# B360C.net
KiCad netlist of a schematic drawn in EAGLE
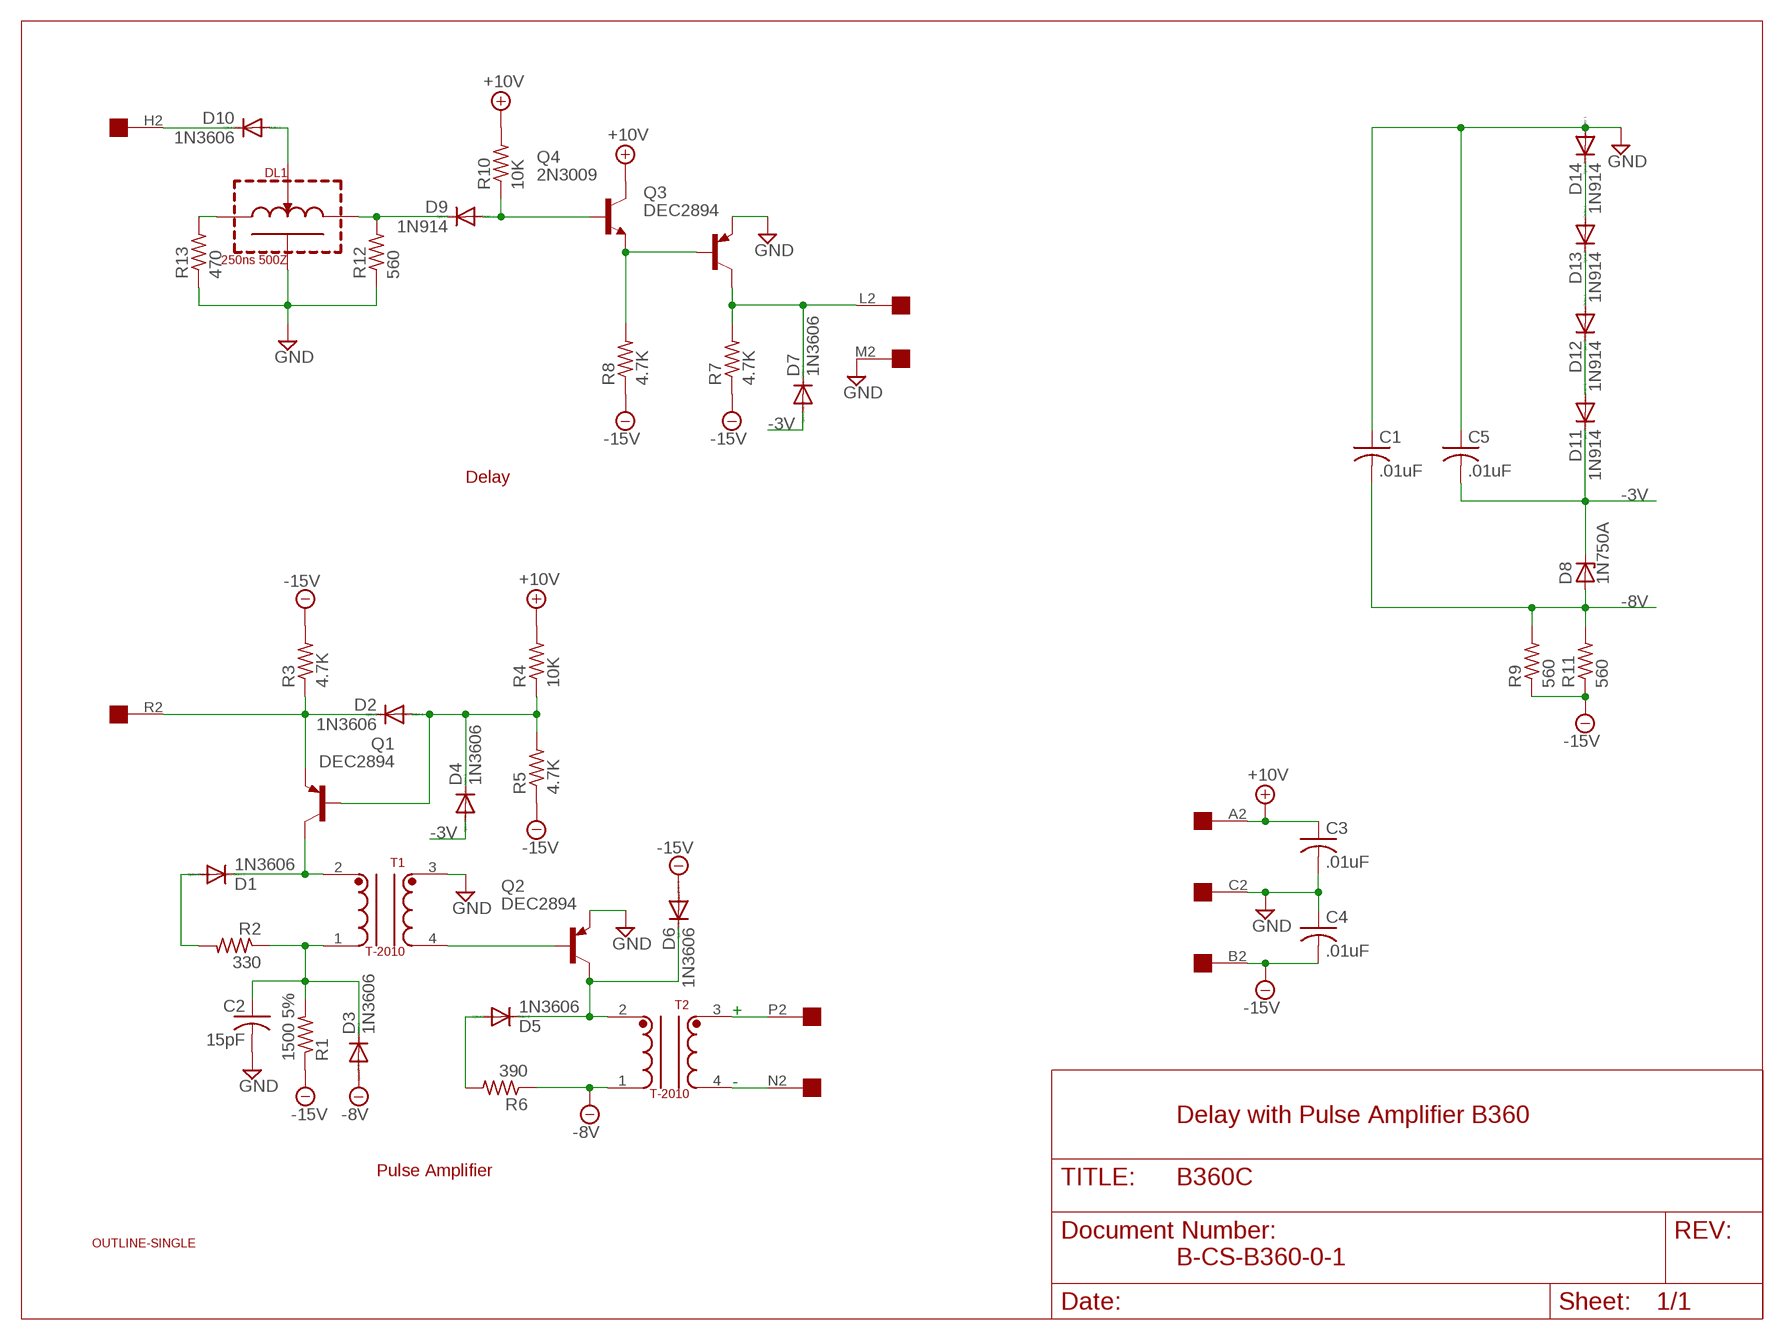
[diagram p0: schematic, sheet 1]

(export (version "E")
  (design (tool "Eeschema 10.0.6"))
  (components
    (comp (ref "C1")
      (value ".01uF")
      (footprint "eagle-import:C050-025X075")
      (libsource (lib "eagle-import") (part "C-US050-025X075"))
    )
    (comp (ref "C2")
      (value "15pF")
      (footprint "eagle-import:C050-025X075")
      (libsource (lib "eagle-import") (part "C-US050-025X075"))
    )
    (comp (ref "C3")
      (value ".01uF")
      (footprint "eagle-import:C050-025X075")
      (libsource (lib "eagle-import") (part "C-US050-025X075"))
    )
    (comp (ref "C4")
      (value ".01uF")
      (footprint "eagle-import:C050-025X075")
      (libsource (lib "eagle-import") (part "C-US050-025X075"))
    )
    (comp (ref "C5")
      (value ".01uF")
      (footprint "eagle-import:C050-025X075")
      (libsource (lib "eagle-import") (part "C-US050-025X075"))
    )
    (comp (ref "D1")
      (value "1N3606")
      (footprint "eagle-import:DO35-10")
      (libsource (lib "eagle-import") (part "1N4148DO35-10"))
    )
    (comp (ref "D2")
      (value "1N3606")
      (footprint "eagle-import:DO35-10")
      (libsource (lib "eagle-import") (part "1N4148DO35-10"))
    )
    (comp (ref "D3")
      (value "1N3606")
      (footprint "eagle-import:DO35-10")
      (libsource (lib "eagle-import") (part "1N4148DO35-10"))
    )
    (comp (ref "D4")
      (value "1N3606")
      (footprint "eagle-import:DO35-10")
      (libsource (lib "eagle-import") (part "1N4148DO35-10"))
    )
    (comp (ref "D5")
      (value "1N3606")
      (footprint "eagle-import:DO35-10")
      (libsource (lib "eagle-import") (part "1N4148DO35-10"))
    )
    (comp (ref "D6")
      (value "1N3606")
      (footprint "eagle-import:DO35-10")
      (libsource (lib "eagle-import") (part "1N4148DO35-10"))
    )
    (comp (ref "D7")
      (value "1N3606")
      (footprint "eagle-import:DO35-10")
      (libsource (lib "eagle-import") (part "1N4148DO35-10"))
    )
    (comp (ref "D8")
      (value "1N750A")
      (footprint "eagle-import:DO35Z10")
      (libsource (lib "eagle-import") (part "ZENER-DIODEDO35Z10"))
    )
    (comp (ref "D9")
      (value "1N914")
      (footprint "eagle-import:DO35-10")
      (libsource (lib "eagle-import") (part "1N4148DO35-10"))
    )
    (comp (ref "D10")
      (value "1N3606")
      (footprint "eagle-import:DO35-10")
      (libsource (lib "eagle-import") (part "1N4148DO35-10"))
    )
    (comp (ref "D11")
      (value "1N914")
      (footprint "eagle-import:DO35-10")
      (libsource (lib "eagle-import") (part "1N4148DO35-10"))
    )
    (comp (ref "D12")
      (value "1N914")
      (footprint "eagle-import:DO35-10")
      (libsource (lib "eagle-import") (part "1N4148DO35-10"))
    )
    (comp (ref "D13")
      (value "1N914")
      (footprint "eagle-import:DO35-10")
      (libsource (lib "eagle-import") (part "1N4148DO35-10"))
    )
    (comp (ref "D14")
      (value "1N914")
      (footprint "eagle-import:DO35-10")
      (libsource (lib "eagle-import") (part "1N4148DO35-10"))
    )
    (comp (ref "DL1")
      (value "250ns 500Z")
      (footprint "eagle-import:DELAYLINE")
      (libsource (lib "eagle-import") (part "DELAYLINE"))
    )
    (comp (ref "Q1")
      (value "DEC2894")
      (footprint "eagle-import:TO39")
      (libsource (lib "eagle-import") (part "2N2904"))
    )
    (comp (ref "Q2")
      (value "DEC2894")
      (footprint "eagle-import:TO39")
      (libsource (lib "eagle-import") (part "2N2904"))
    )
    (comp (ref "Q3")
      (value "DEC2894")
      (footprint "eagle-import:TO39")
      (libsource (lib "eagle-import") (part "2N2904"))
    )
    (comp (ref "Q4")
      (value "2N3009")
      (footprint "eagle-import:TO39")
      (libsource (lib "eagle-import") (part "-NPN-TO39-EBC2N2102"))
    )
    (comp (ref "R1")
      (value "1500 5%")
      (footprint "eagle-import:0207_10")
      (libsource (lib "eagle-import") (part "R-US_0207/10"))
    )
    (comp (ref "R2")
      (value "330")
      (footprint "eagle-import:0207_10")
      (libsource (lib "eagle-import") (part "R-US_0207/10"))
    )
    (comp (ref "R3")
      (value "4.7K")
      (footprint "eagle-import:0207_10")
      (libsource (lib "eagle-import") (part "R-US_0207/10"))
    )
    (comp (ref "R4")
      (value "10K")
      (footprint "eagle-import:0207_10")
      (libsource (lib "eagle-import") (part "R-US_0207/10"))
    )
    (comp (ref "R5")
      (value "4.7K")
      (footprint "eagle-import:0207_10")
      (libsource (lib "eagle-import") (part "R-US_0207/10"))
    )
    (comp (ref "R6")
      (value "390")
      (footprint "eagle-import:0207_10")
      (libsource (lib "eagle-import") (part "R-US_0207/10"))
    )
    (comp (ref "R7")
      (value "4.7K")
      (footprint "eagle-import:0207_10")
      (libsource (lib "eagle-import") (part "R-US_0207/10"))
    )
    (comp (ref "R8")
      (value "4.7K")
      (footprint "eagle-import:0207_10")
      (libsource (lib "eagle-import") (part "R-US_0207/10"))
    )
    (comp (ref "R9")
      (value "560")
      (footprint "eagle-import:0207_10")
      (libsource (lib "eagle-import") (part "R-US_0207/10"))
    )
    (comp (ref "R10")
      (value "10K")
      (footprint "eagle-import:0207_10")
      (libsource (lib "eagle-import") (part "R-US_0207/10"))
    )
    (comp (ref "R11")
      (value "560")
      (footprint "eagle-import:0207_10")
      (libsource (lib "eagle-import") (part "R-US_0207/10"))
    )
    (comp (ref "R12")
      (value "560")
      (footprint "eagle-import:0207_10")
      (libsource (lib "eagle-import") (part "R-US_0207/10"))
    )
    (comp (ref "R13")
      (value "470")
      (footprint "eagle-import:0207_10")
      (libsource (lib "eagle-import") (part "R-US_0207/10"))
    )
    (comp (ref "T1")
      (value "T-2010")
      (footprint "eagle-import:TRANSFORMER2")
      (libsource (lib "eagle-import") (part "T-2010"))
    )
    (comp (ref "T2")
      (value "T-2010")
      (footprint "eagle-import:TRANSFORMER2")
      (libsource (lib "eagle-import") (part "T-2010"))
    )
    (comp (ref "U$1")
      (value "OUTLINE-SINGLE")
      (footprint "eagle-import:SINGLE")
      (libsource (lib "eagle-import") (part "OUTLINE-SINGLE"))
    )
    (comp (ref "U$2")
      (value "EDGE-1")
      (footprint "eagle-import:EDGE-CON1")
      (libsource (lib "eagle-import") (part "EDGE-1"))
    )
  )
  (nets
    (net (code "1") (name "+10V") (class "Default")
      (node (ref "C3") (pin "1") (pinfunction "1_1") (pintype "passive"))
      (node (ref "Q4") (pin "3") (pinfunction "C_3") (pintype "passive"))
      (node (ref "R10") (pin "2") (pinfunction "2_2") (pintype "passive"))
      (node (ref "R4") (pin "2") (pinfunction "2_2") (pintype "passive"))
      (node (ref "U$2") (pin "A2") (pinfunction "1_A2") (pintype "bidirectional"))
    )
    (net (code "2") (name "-8V") (class "Default")
      (node (ref "C1") (pin "2") (pinfunction "2_2") (pintype "passive"))
      (node (ref "D3") (pin "A") (pinfunction "A_A") (pintype "passive"))
      (node (ref "D8") (pin "A") (pinfunction "A_A") (pintype "passive"))
      (node (ref "R11") (pin "2") (pinfunction "2_2") (pintype "passive"))
      (node (ref "R6") (pin "1") (pinfunction "1_1") (pintype "passive"))
      (node (ref "R9") (pin "2") (pinfunction "2_2") (pintype "passive"))
      (node (ref "T2") (pin "1") (pinfunction "P$5_1") (pintype "passive"))
    )
    (net (code "3") (name "-15V") (class "Default")
      (node (ref "C4") (pin "2") (pinfunction "2_2") (pintype "passive"))
      (node (ref "D6") (pin "A") (pinfunction "A_A") (pintype "passive"))
      (node (ref "R1") (pin "1") (pinfunction "1_1") (pintype "passive"))
      (node (ref "R11") (pin "1") (pinfunction "1_1") (pintype "passive"))
      (node (ref "R3") (pin "2") (pinfunction "2_2") (pintype "passive"))
      (node (ref "R5") (pin "1") (pinfunction "1_1") (pintype "passive"))
      (node (ref "R7") (pin "1") (pinfunction "1_1") (pintype "passive"))
      (node (ref "R8") (pin "1") (pinfunction "1_1") (pintype "passive"))
      (node (ref "R9") (pin "1") (pinfunction "1_1") (pintype "passive"))
      (node (ref "U$2") (pin "B2") (pinfunction "1_B2") (pintype "bidirectional"))
    )
    (net (code "4") (name "/-3V") (class "Default")
      (node (ref "C5") (pin "2") (pinfunction "2_2") (pintype "passive"))
      (node (ref "D11") (pin "C") (pinfunction "C_C") (pintype "passive"))
      (node (ref "D4") (pin "A") (pinfunction "A_A") (pintype "passive"))
      (node (ref "D7") (pin "A") (pinfunction "A_A") (pintype "passive"))
      (node (ref "D8") (pin "C") (pinfunction "C_C") (pintype "passive"))
    )
    (net (code "5") (name "GND") (class "Default")
      (node (ref "C1") (pin "1") (pinfunction "1_1") (pintype "passive"))
      (node (ref "C2") (pin "2") (pinfunction "2_2") (pintype "passive"))
      (node (ref "C3") (pin "2") (pinfunction "2_2") (pintype "passive"))
      (node (ref "C4") (pin "1") (pinfunction "1_1") (pintype "passive"))
      (node (ref "C5") (pin "1") (pinfunction "1_1") (pintype "passive"))
      (node (ref "D14") (pin "A") (pinfunction "A_A") (pintype "passive"))
      (node (ref "DL1") (pin "G") (pinfunction "G_G") (pintype "passive"))
      (node (ref "Q2") (pin "1") (pinfunction "E_1") (pintype "passive"))
      (node (ref "Q3") (pin "1") (pinfunction "E_1") (pintype "passive"))
      (node (ref "R12") (pin "1") (pinfunction "1_1") (pintype "passive"))
      (node (ref "R13") (pin "1") (pinfunction "1_1") (pintype "passive"))
      (node (ref "T1") (pin "3") (pinfunction "P$2_3") (pintype "passive"))
      (node (ref "U$2") (pin "C2") (pinfunction "1_C2") (pintype "bidirectional"))
      (node (ref "U$2") (pin "M2") (pinfunction "1_M2") (pintype "bidirectional"))
    )
    (net (code "6") (name "Net-(D1-PadA)") (class "Default")
      (node (ref "D1") (pin "A") (pinfunction "A_A") (pintype "passive"))
      (node (ref "R2") (pin "2") (pinfunction "2_2") (pintype "passive"))
    )
    (net (code "7") (name "Net-(D5-PadA)") (class "Default")
      (node (ref "D5") (pin "A") (pinfunction "A_A") (pintype "passive"))
      (node (ref "R6") (pin "2") (pinfunction "2_2") (pintype "passive"))
    )
    (net (code "8") (name "Net-(D9-PadC)") (class "Default")
      (node (ref "D9") (pin "C") (pinfunction "C_C") (pintype "passive"))
      (node (ref "DL1") (pin "L") (pinfunction "L_L") (pintype "passive"))
      (node (ref "R12") (pin "2") (pinfunction "2_2") (pintype "passive"))
    )
    (net (code "9") (name "Net-(D10-PadA)") (class "Default")
      (node (ref "D10") (pin "A") (pinfunction "A_A") (pintype "passive"))
      (node (ref "DL1") (pin "V") (pinfunction "V_V") (pintype "passive"))
    )
    (net (code "10") (name "Net-(D11-PadA)") (class "Default")
      (node (ref "D11") (pin "A") (pinfunction "A_A") (pintype "passive"))
      (node (ref "D12") (pin "C") (pinfunction "C_C") (pintype "passive"))
    )
    (net (code "11") (name "Net-(D12-PadA)") (class "Default")
      (node (ref "D12") (pin "A") (pinfunction "A_A") (pintype "passive"))
      (node (ref "D13") (pin "C") (pinfunction "C_C") (pintype "passive"))
    )
    (net (code "12") (name "Net-(D13-PadA)") (class "Default")
      (node (ref "D13") (pin "A") (pinfunction "A_A") (pintype "passive"))
      (node (ref "D14") (pin "C") (pinfunction "C_C") (pintype "passive"))
    )
    (net (code "13") (name "Net-(DL1-PadR)") (class "Default")
      (node (ref "DL1") (pin "R") (pinfunction "R_R") (pintype "passive"))
      (node (ref "R13") (pin "2") (pinfunction "2_2") (pintype "passive"))
    )
    (net (code "14") (name "Net-(Q1-B)") (class "Default")
      (node (ref "D2") (pin "A") (pinfunction "A_A") (pintype "passive"))
      (node (ref "D4") (pin "C") (pinfunction "C_C") (pintype "passive"))
      (node (ref "Q1") (pin "2") (pinfunction "B_2") (pintype "passive"))
      (node (ref "R4") (pin "1") (pinfunction "1_1") (pintype "passive"))
      (node (ref "R5") (pin "2") (pinfunction "2_2") (pintype "passive"))
    )
    (net (code "15") (name "Net-(Q1-C)") (class "Default")
      (node (ref "D1") (pin "C") (pinfunction "C_C") (pintype "passive"))
      (node (ref "Q1") (pin "3") (pinfunction "C_3") (pintype "passive"))
      (node (ref "T1") (pin "2") (pinfunction "P$4_2") (pintype "passive"))
    )
    (net (code "16") (name "Net-(Q1-E)") (class "Default")
      (node (ref "D2") (pin "C") (pinfunction "C_C") (pintype "passive"))
      (node (ref "Q1") (pin "1") (pinfunction "E_1") (pintype "passive"))
      (node (ref "R3") (pin "1") (pinfunction "1_1") (pintype "passive"))
      (node (ref "U$2") (pin "R2") (pinfunction "1_R2") (pintype "bidirectional"))
    )
    (net (code "17") (name "Net-(Q2-B)") (class "Default")
      (node (ref "Q2") (pin "2") (pinfunction "B_2") (pintype "passive"))
      (node (ref "T1") (pin "4") (pinfunction "P$7_4") (pintype "passive"))
    )
    (net (code "18") (name "Net-(Q2-C)") (class "Default")
      (node (ref "D5") (pin "C") (pinfunction "C_C") (pintype "passive"))
      (node (ref "D6") (pin "C") (pinfunction "C_C") (pintype "passive"))
      (node (ref "Q2") (pin "3") (pinfunction "C_3") (pintype "passive"))
      (node (ref "T2") (pin "2") (pinfunction "P$4_2") (pintype "passive"))
    )
    (net (code "19") (name "Net-(Q3-B)") (class "Default")
      (node (ref "Q3") (pin "2") (pinfunction "B_2") (pintype "passive"))
      (node (ref "Q4") (pin "1") (pinfunction "E_1") (pintype "passive"))
      (node (ref "R8") (pin "2") (pinfunction "2_2") (pintype "passive"))
    )
    (net (code "20") (name "Net-(Q3-C)") (class "Default")
      (node (ref "D7") (pin "C") (pinfunction "C_C") (pintype "passive"))
      (node (ref "Q3") (pin "3") (pinfunction "C_3") (pintype "passive"))
      (node (ref "R7") (pin "2") (pinfunction "2_2") (pintype "passive"))
      (node (ref "U$2") (pin "L2") (pinfunction "1_L2") (pintype "bidirectional"))
    )
    (net (code "21") (name "Net-(Q4-B)") (class "Default")
      (node (ref "D9") (pin "A") (pinfunction "A_A") (pintype "passive"))
      (node (ref "Q4") (pin "2") (pinfunction "B_2") (pintype "passive"))
      (node (ref "R10") (pin "1") (pinfunction "1_1") (pintype "passive"))
    )
    (net (code "22") (name "Net-(T1-P$5)") (class "Default")
      (node (ref "C2") (pin "1") (pinfunction "1_1") (pintype "passive"))
      (node (ref "D3") (pin "C") (pinfunction "C_C") (pintype "passive"))
      (node (ref "R1") (pin "2") (pinfunction "2_2") (pintype "passive"))
      (node (ref "R2") (pin "1") (pinfunction "1_1") (pintype "passive"))
      (node (ref "T1") (pin "1") (pinfunction "P$5_1") (pintype "passive"))
    )
    (net (code "23") (name "Net-(T2-P$2)") (class "Default")
      (node (ref "T2") (pin "3") (pinfunction "P$2_3") (pintype "passive"))
      (node (ref "U$2") (pin "P2") (pinfunction "1_P2") (pintype "bidirectional"))
    )
    (net (code "24") (name "Net-(T2-P$7)") (class "Default")
      (node (ref "T2") (pin "4") (pinfunction "P$7_4") (pintype "passive"))
      (node (ref "U$2") (pin "N2") (pinfunction "1_N2") (pintype "bidirectional"))
    )
    (net (code "25") (name "Net-(U$2G-1)") (class "Default")
      (node (ref "D10") (pin "C") (pinfunction "C_C") (pintype "passive"))
      (node (ref "U$2") (pin "H2") (pinfunction "1_H2") (pintype "bidirectional"))
    )
  )
)
